# ocd_redraw.net
KiCad netlist of a schematic drawn in EAGLE
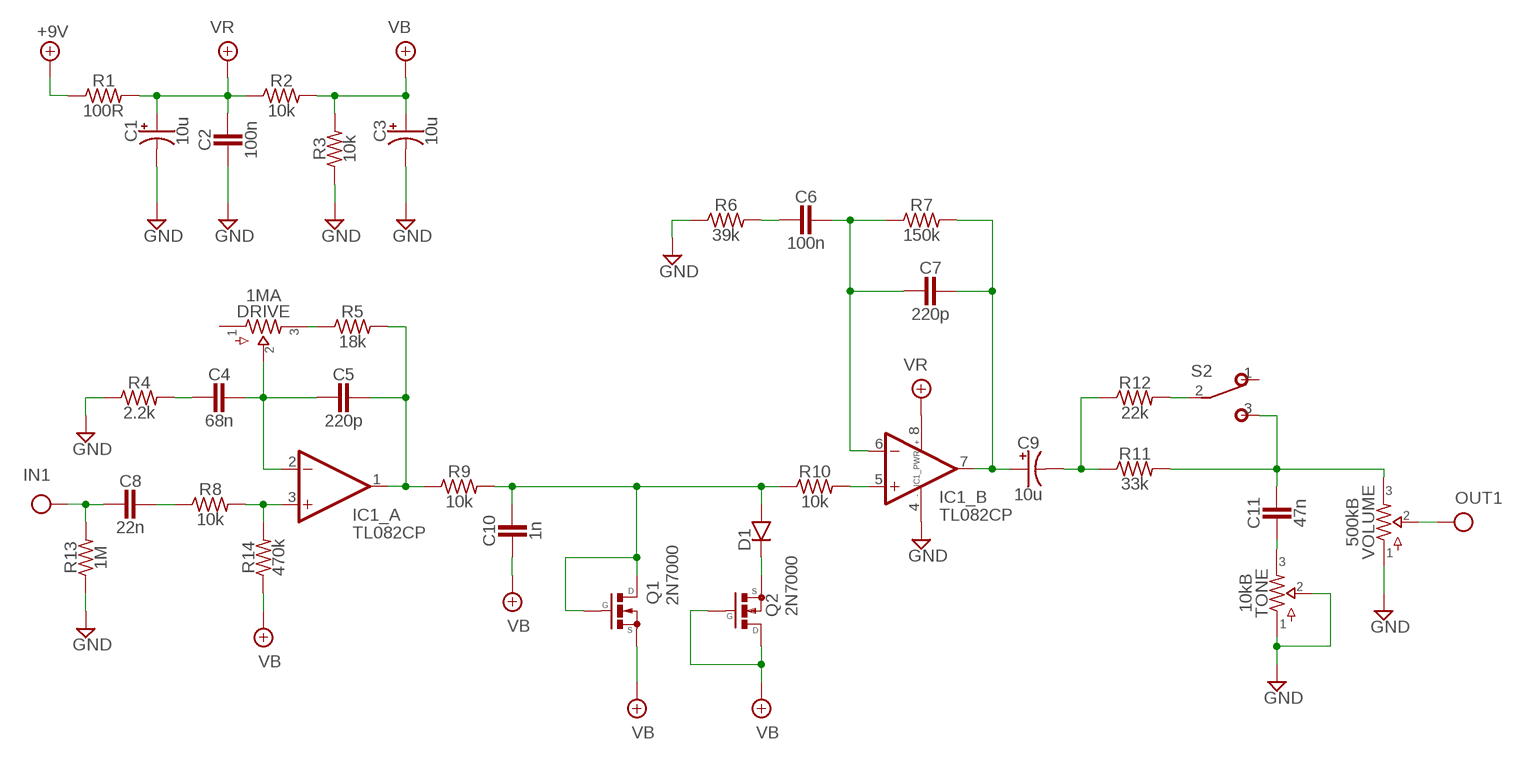
[diagram p0: schematic, sheet 1]

(export (version "E")
  (design (tool "Eeschema 10.0.6"))
  (components
    (comp (ref "C1")
      (value "10u")
      (footprint "eagle-import:050_020")
      (libsource (lib "eagle-import") (part "0500"))
    )
    (comp (ref "C2")
      (value "100n")
      (footprint "eagle-import:BOX_SMALL")
      (libsource (lib "eagle-import") (part "CER/FILMBOX.1"))
    )
    (comp (ref "C3")
      (value "10u")
      (footprint "eagle-import:050_020")
      (libsource (lib "eagle-import") (part "0500"))
    )
    (comp (ref "C4")
      (value "68n")
      (footprint "eagle-import:BOX_SMALL")
      (libsource (lib "eagle-import") (part "CER/FILMBOX.1"))
    )
    (comp (ref "C5")
      (value "220p")
      (footprint "eagle-import:BOX_SMALL")
      (libsource (lib "eagle-import") (part "CER/FILMBOX.1"))
    )
    (comp (ref "C6")
      (value "100n")
      (footprint "eagle-import:BOX_SMALL")
      (libsource (lib "eagle-import") (part "CER/FILMBOX.1"))
    )
    (comp (ref "C7")
      (value "220p")
      (footprint "eagle-import:BOX_SMALL")
      (libsource (lib "eagle-import") (part "CER/FILMBOX.1"))
    )
    (comp (ref "C8")
      (value "22n")
      (footprint "eagle-import:BOX_SMALL")
      (libsource (lib "eagle-import") (part "CER/FILMBOX.1"))
    )
    (comp (ref "C9")
      (value "10u")
      (footprint "eagle-import:050_020")
      (libsource (lib "eagle-import") (part "0500"))
    )
    (comp (ref "C10")
      (value "1n")
      (footprint "eagle-import:BOX_SMALL")
      (libsource (lib "eagle-import") (part "CER/FILMBOX.1"))
    )
    (comp (ref "C11")
      (value "47n")
      (footprint "eagle-import:BOX_SMALL")
      (libsource (lib "eagle-import") (part "CER/FILMBOX.1"))
    )
    (comp (ref "D1")
      (value "DO41.2")
      (footprint "eagle-import:DO41-2")
      (libsource (lib "eagle-import") (part "DO41.2"))
    )
    (comp (ref "DRIVE")
      (value "1MA")
      (footprint "eagle-import:16MM")
      (libsource (lib "eagle-import") (part "POTS16MM"))
    )
    (comp (ref "IC1")
      (value "TL082CP")
      (footprint "eagle-import:DIL0")
      (libsource (lib "eagle-import") (part "DUALTH"))
    )
    (comp (ref "Q1")
      (value "2N7000")
      (footprint "eagle-import:TO92-")
      (libsource (lib "eagle-import") (part "2N7000"))
    )
    (comp (ref "Q2")
      (value "2N7000")
      (footprint "eagle-import:TO92-")
      (libsource (lib "eagle-import") (part "2N7000"))
    )
    (comp (ref "R1")
      (value "100R")
      (footprint "eagle-import:R0207_3")
      (libsource (lib "eagle-import") (part "R_.3B"))
    )
    (comp (ref "R2")
      (value "10k")
      (footprint "eagle-import:R0207_3")
      (libsource (lib "eagle-import") (part "R_.3B"))
    )
    (comp (ref "R3")
      (value "10k")
      (footprint "eagle-import:R0207_3")
      (libsource (lib "eagle-import") (part "R_.3B"))
    )
    (comp (ref "R4")
      (value "2.2k")
      (footprint "eagle-import:R0207_3")
      (libsource (lib "eagle-import") (part "R_.3B"))
    )
    (comp (ref "R5")
      (value "18k")
      (footprint "eagle-import:R0207_3")
      (libsource (lib "eagle-import") (part "R_.3B"))
    )
    (comp (ref "R6")
      (value "39k")
      (footprint "eagle-import:R0207_3")
      (libsource (lib "eagle-import") (part "R_.3B"))
    )
    (comp (ref "R7")
      (value "150k")
      (footprint "eagle-import:R0207_3")
      (libsource (lib "eagle-import") (part "R_.3B"))
    )
    (comp (ref "R8")
      (value "10k")
      (footprint "eagle-import:R0207_3")
      (libsource (lib "eagle-import") (part "R_.3B"))
    )
    (comp (ref "R9")
      (value "10k")
      (footprint "eagle-import:R0207_3")
      (libsource (lib "eagle-import") (part "R_.3B"))
    )
    (comp (ref "R10")
      (value "10k")
      (footprint "eagle-import:R0207_3")
      (libsource (lib "eagle-import") (part "R_.3B"))
    )
    (comp (ref "R11")
      (value "33k")
      (footprint "eagle-import:R0207_3")
      (libsource (lib "eagle-import") (part "R_.3B"))
    )
    (comp (ref "R12")
      (value "22k")
      (footprint "eagle-import:R0207_3")
      (libsource (lib "eagle-import") (part "R_.3B"))
    )
    (comp (ref "R13")
      (value "1M")
      (footprint "eagle-import:R0207_3")
      (libsource (lib "eagle-import") (part "R_.3B"))
    )
    (comp (ref "R14")
      (value "470k")
      (footprint "eagle-import:R0207_3")
      (libsource (lib "eagle-import") (part "R_.3B"))
    )
    (comp (ref "S2")
      (value "SPDT")
      (footprint "eagle-import:M9040P")
      (libsource (lib "eagle-import") (part "SPDT"))
    )
    (comp (ref "TONE")
      (value "10kB")
      (footprint "eagle-import:16MM")
      (libsource (lib "eagle-import") (part "POTS16MM"))
    )
    (comp (ref "VOLUME")
      (value "500kB")
      (footprint "eagle-import:16MM")
      (libsource (lib "eagle-import") (part "POTS16MM"))
    )
  )
  (nets
    (net (code "1") (name "+9V") (class "Default")
      (node (ref "R1") (pin "1") (pinfunction "1_1") (pintype "passive"))
    )
    (net (code "2") (name "GND") (class "Default")
      (node (ref "C1") (pin "-") (pinfunction "-_-") (pintype "passive"))
      (node (ref "C2") (pin "2") (pinfunction "2_2") (pintype "passive"))
      (node (ref "C3") (pin "-") (pinfunction "-_-") (pintype "passive"))
      (node (ref "IC1") (pin "4") (pinfunction "V-_4") (pintype "power_in"))
      (node (ref "R13") (pin "1") (pinfunction "1_1") (pintype "passive"))
      (node (ref "R3") (pin "1") (pinfunction "1_1") (pintype "passive"))
      (node (ref "R4") (pin "1") (pinfunction "1_1") (pintype "passive"))
      (node (ref "R6") (pin "1") (pinfunction "1_1") (pintype "passive"))
      (node (ref "TONE") (pin "1") (pinfunction "1_1") (pintype "passive"))
      (node (ref "TONE") (pin "2") (pinfunction "2_2") (pintype "passive"))
      (node (ref "VOLUME") (pin "1") (pinfunction "1_1") (pintype "passive"))
    )
    (net (code "3") (name "IN") (class "Default")
      (node (ref "C8") (pin "2") (pinfunction "2_2") (pintype "passive"))
      (node (ref "R13") (pin "2") (pinfunction "2_2") (pintype "passive"))
    )
    (net (code "4") (name "Net-(C4-Pad2)") (class "Default")
      (node (ref "C4") (pin "2") (pinfunction "2_2") (pintype "passive"))
      (node (ref "R4") (pin "2") (pinfunction "2_2") (pintype "passive"))
    )
    (net (code "5") (name "Net-(C6-Pad2)") (class "Default")
      (node (ref "C6") (pin "2") (pinfunction "2_2") (pintype "passive"))
      (node (ref "R6") (pin "2") (pinfunction "2_2") (pintype "passive"))
    )
    (net (code "6") (name "Net-(C8-Pad1)") (class "Default")
      (node (ref "C8") (pin "1") (pinfunction "1_1") (pintype "passive"))
      (node (ref "R8") (pin "1") (pinfunction "1_1") (pintype "passive"))
    )
    (net (code "7") (name "Net-(C9-Pad-)") (class "Default")
      (node (ref "C9") (pin "-") (pinfunction "-_-") (pintype "passive"))
      (node (ref "R11") (pin "1") (pinfunction "1_1") (pintype "passive"))
      (node (ref "R12") (pin "1") (pinfunction "1_1") (pintype "passive"))
    )
    (net (code "8") (name "Net-(C11-Pad2)") (class "Default")
      (node (ref "C11") (pin "2") (pinfunction "2_2") (pintype "passive"))
      (node (ref "TONE") (pin "3") (pinfunction "3_3") (pintype "passive"))
    )
    (net (code "9") (name "Net-(DRIVE-Pad3)") (class "Default")
      (node (ref "DRIVE") (pin "3") (pinfunction "3_3") (pintype "passive"))
      (node (ref "R5") (pin "1") (pinfunction "1_1") (pintype "passive"))
    )
    (net (code "10") (name "Net-(IC1A-+IN)") (class "Default")
      (node (ref "IC1") (pin "3") (pinfunction "+IN_3") (pintype "input"))
      (node (ref "R14") (pin "2") (pinfunction "2_2") (pintype "passive"))
      (node (ref "R8") (pin "2") (pinfunction "2_2") (pintype "passive"))
    )
    (net (code "11") (name "Net-(IC1A--IN)") (class "Default")
      (node (ref "C4") (pin "1") (pinfunction "1_1") (pintype "passive"))
      (node (ref "C5") (pin "2") (pinfunction "2_2") (pintype "passive"))
      (node (ref "DRIVE") (pin "2") (pinfunction "2_2") (pintype "passive"))
      (node (ref "IC1") (pin "2") (pinfunction "-IN_2") (pintype "input"))
    )
    (net (code "12") (name "Net-(IC1A-OUT)") (class "Default")
      (node (ref "C5") (pin "1") (pinfunction "1_1") (pintype "passive"))
      (node (ref "IC1") (pin "1") (pinfunction "OUT_1") (pintype "output"))
      (node (ref "R5") (pin "2") (pinfunction "2_2") (pintype "passive"))
      (node (ref "R9") (pin "1") (pinfunction "1_1") (pintype "passive"))
    )
    (net (code "13") (name "Net-(IC1B-+IN)") (class "Default")
      (node (ref "IC1") (pin "5") (pinfunction "+IN_5") (pintype "input"))
      (node (ref "R10") (pin "2") (pinfunction "2_2") (pintype "passive"))
    )
    (net (code "14") (name "Net-(IC1B--IN)") (class "Default")
      (node (ref "C6") (pin "1") (pinfunction "1_1") (pintype "passive"))
      (node (ref "C7") (pin "2") (pinfunction "2_2") (pintype "passive"))
      (node (ref "IC1") (pin "6") (pinfunction "-IN_6") (pintype "input"))
      (node (ref "R7") (pin "1") (pinfunction "1_1") (pintype "passive"))
    )
    (net (code "15") (name "Net-(IC1B-OUT)") (class "Default")
      (node (ref "C7") (pin "1") (pinfunction "1_1") (pintype "passive"))
      (node (ref "C9") (pin "+") (pinfunction "+_+") (pintype "passive"))
      (node (ref "IC1") (pin "7") (pinfunction "OUT_7") (pintype "output"))
      (node (ref "R7") (pin "2") (pinfunction "2_2") (pintype "passive"))
    )
    (net (code "16") (name "Net-(Q1-D)") (class "Default")
      (node (ref "C10") (pin "1") (pinfunction "1_1") (pintype "passive"))
      (node (ref "D1") (pin "A") (pinfunction "A_A") (pintype "passive"))
      (node (ref "Q1") (pin "1") (pinfunction "D_1") (pintype "passive"))
      (node (ref "Q1") (pin "2") (pinfunction "G_2") (pintype "passive"))
      (node (ref "R10") (pin "1") (pinfunction "1_1") (pintype "passive"))
      (node (ref "R9") (pin "2") (pinfunction "2_2") (pintype "passive"))
    )
    (net (code "17") (name "Net-(Q2-S)") (class "Default")
      (node (ref "D1") (pin "C") (pinfunction "C_C") (pintype "passive"))
      (node (ref "Q2") (pin "3") (pinfunction "S_3") (pintype "passive"))
    )
    (net (code "18") (name "Net-(S2-P)") (class "Default")
      (node (ref "R12") (pin "2") (pinfunction "2_2") (pintype "passive"))
      (node (ref "S2") (pin "2") (pinfunction "P_2") (pintype "passive"))
    )
    (net (code "19") (name "Net-(S2-S)") (class "Default")
      (node (ref "C11") (pin "1") (pinfunction "1_1") (pintype "passive"))
      (node (ref "R11") (pin "2") (pinfunction "2_2") (pintype "passive"))
      (node (ref "S2") (pin "3") (pinfunction "S_3") (pintype "passive"))
      (node (ref "VOLUME") (pin "3") (pinfunction "3_3") (pintype "passive"))
    )
    (net (code "20") (name "OUT") (class "Default")
      (node (ref "VOLUME") (pin "2") (pinfunction "2_2") (pintype "passive"))
    )
    (net (code "21") (name "VB") (class "Default")
      (node (ref "C10") (pin "2") (pinfunction "2_2") (pintype "passive"))
      (node (ref "C3") (pin "+") (pinfunction "+_+") (pintype "passive"))
      (node (ref "Q1") (pin "3") (pinfunction "S_3") (pintype "passive"))
      (node (ref "Q2") (pin "1") (pinfunction "D_1") (pintype "passive"))
      (node (ref "Q2") (pin "2") (pinfunction "G_2") (pintype "passive"))
      (node (ref "R14") (pin "1") (pinfunction "1_1") (pintype "passive"))
      (node (ref "R2") (pin "2") (pinfunction "2_2") (pintype "passive"))
      (node (ref "R3") (pin "2") (pinfunction "2_2") (pintype "passive"))
    )
    (net (code "22") (name "VR") (class "Default")
      (node (ref "C1") (pin "+") (pinfunction "+_+") (pintype "passive"))
      (node (ref "C2") (pin "1") (pinfunction "1_1") (pintype "passive"))
      (node (ref "IC1") (pin "8") (pinfunction "V+_8") (pintype "power_in"))
      (node (ref "R1") (pin "2") (pinfunction "2_2") (pintype "passive"))
      (node (ref "R2") (pin "1") (pinfunction "1_1") (pintype "passive"))
    )
    (net (code "23") (name "unconnected-(DRIVE-Pad1)") (class "Default")
      (node (ref "DRIVE") (pin "1") (pinfunction "1_1") (pintype "passive"))
    )
    (net (code "24") (name "unconnected-(S2-O-Pad1)") (class "Default")
      (node (ref "S2") (pin "1") (pinfunction "O_1") (pintype "passive"))
    )
  )
)
